# MPPTBatteryCharger.net
KiCad netlist of a schematic drawn in EAGLE
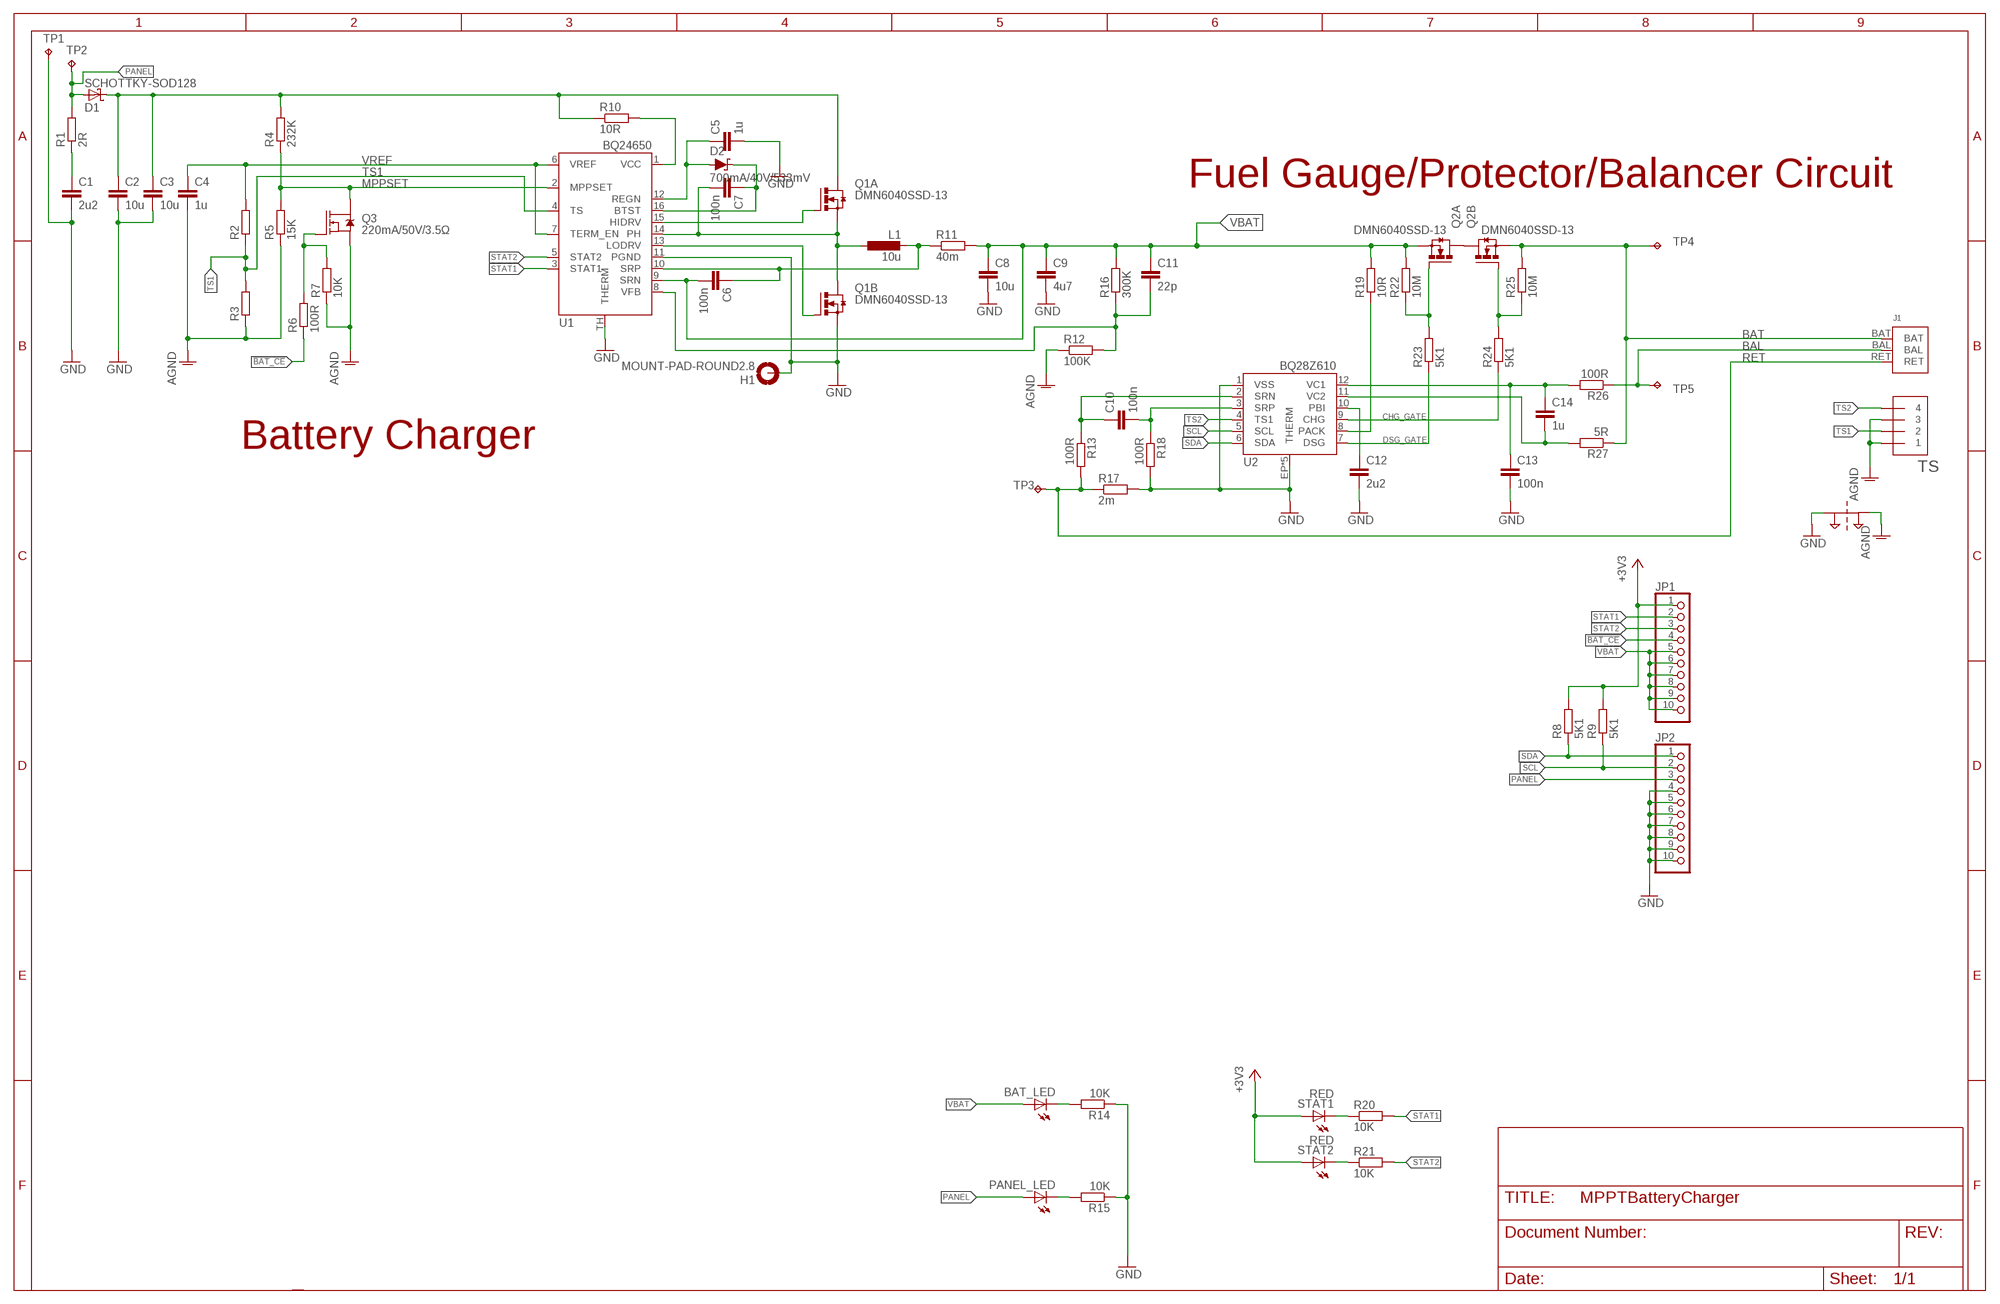
[diagram p0: schematic, sheet 1]

(export (version "E")
  (design (tool "Eeschema 10.0.6"))
  (components
    (comp (ref "BAT_LED")
      (value "LEDCHIP-LED0603")
      (footprint "eagle-import:CHIP-LED0603")
      (libsource (lib "eagle-import") (part "LEDCHIP-LED0603"))
    )
    (comp (ref "C1")
      (value "2u2")
      (footprint "eagle-import:C0603")
      (libsource (lib "eagle-import") (part "C-EUC0603"))
    )
    (comp (ref "C2")
      (value "10u")
      (footprint "eagle-import:C1210")
      (libsource (lib "eagle-import") (part "C-EUC1210"))
    )
    (comp (ref "C3")
      (value "10u")
      (footprint "eagle-import:C1210")
      (libsource (lib "eagle-import") (part "C-EUC1210"))
    )
    (comp (ref "C4")
      (value "1u")
      (footprint "eagle-import:C0603")
      (libsource (lib "eagle-import") (part "C-EUC0603"))
    )
    (comp (ref "C5")
      (value "1u")
      (footprint "eagle-import:C0603")
      (libsource (lib "eagle-import") (part "C-EUC0603"))
    )
    (comp (ref "C6")
      (value "100n")
      (footprint "eagle-import:C0603")
      (libsource (lib "eagle-import") (part "C-EUC0603"))
    )
    (comp (ref "C7")
      (value "100n")
      (footprint "eagle-import:C0603")
      (libsource (lib "eagle-import") (part "C-EUC0603"))
    )
    (comp (ref "C8")
      (value "10u")
      (footprint "eagle-import:C1210")
      (libsource (lib "eagle-import") (part "C-EUC1210"))
    )
    (comp (ref "C9")
      (value "4u7")
      (footprint "eagle-import:C1210")
      (libsource (lib "eagle-import") (part "C-EUC1210"))
    )
    (comp (ref "C10")
      (value "100n")
      (footprint "eagle-import:C0603")
      (libsource (lib "eagle-import") (part "C-EUC0603"))
    )
    (comp (ref "C11")
      (value "22p")
      (footprint "eagle-import:C0603")
      (libsource (lib "eagle-import") (part "C-EUC0603"))
    )
    (comp (ref "C12")
      (value "2u2")
      (footprint "eagle-import:C0603")
      (libsource (lib "eagle-import") (part "C-EUC0603"))
    )
    (comp (ref "C13")
      (value "100n")
      (footprint "eagle-import:C0603")
      (libsource (lib "eagle-import") (part "C-EUC0603"))
    )
    (comp (ref "C14")
      (value "1u")
      (footprint "eagle-import:C0603")
      (libsource (lib "eagle-import") (part "C-EUC0603"))
    )
    (comp (ref "D1")
      (value "SCHOTTKY-SOD128")
      (footprint "eagle-import:SOD-128")
      (libsource (lib "eagle-import") (part "SCHOTTKY-SOD128"))
    )
    (comp (ref "D2")
      (value "700mA/40V/533mV")
      (footprint "eagle-import:SOT23-3")
      (libsource (lib "eagle-import") (part "DIODE-SCHOTTKY-ZLLS500"))
    )
    (comp (ref "H1")
      (value "MOUNT-PAD-ROUND2.8")
      (footprint "eagle-import:2,8-PAD")
      (libsource (lib "eagle-import") (part "MOUNT-PAD-ROUND2.8"))
    )
    (comp (ref "J1")
      (value "2S-BATTERYSMD")
      (footprint "eagle-import:JST-XH3-SMD")
      (libsource (lib "eagle-import") (part "2S-BATTERYSMD"))
    )
    (comp (ref "JP1")
      (value "PINHD-1X10")
      (footprint "eagle-import:1X10")
      (libsource (lib "eagle-import") (part "PINHD-1X10"))
    )
    (comp (ref "JP2")
      (value "PINHD-1X10")
      (footprint "eagle-import:1X10")
      (libsource (lib "eagle-import") (part "PINHD-1X10"))
    )
    (comp (ref "L1")
      (value "10u")
      (footprint "eagle-import:DG6050")
      (libsource (lib "eagle-import") (part "INDUCTOR-DG6050"))
    )
    (comp (ref "PANEL_LED")
      (value "LEDCHIP-LED0603")
      (footprint "eagle-import:CHIP-LED0603")
      (libsource (lib "eagle-import") (part "LEDCHIP-LED0603"))
    )
    (comp (ref "Q1")
      (value "DMN6040SSD-13")
      (footprint "eagle-import:SO-08")
      (libsource (lib "eagle-import") (part "IRF8313P"))
    )
    (comp (ref "Q2")
      (value "DMN6040SSD-13")
      (footprint "eagle-import:SO-08")
      (libsource (lib "eagle-import") (part "IRF8313P"))
    )
    (comp (ref "Q3")
      (value "220mA/50V/3.5Ω")
      (footprint "eagle-import:SOT23-3")
      (libsource (lib "eagle-import") (part "MOSFET-NCH-BSS138"))
    )
    (comp (ref "R1")
      (value "2R")
      (footprint "eagle-import:R0603")
      (libsource (lib "eagle-import") (part "R-EU_R0603"))
    )
    (comp (ref "R2")
      (value "R-EU_R0603")
      (footprint "eagle-import:R0603")
      (libsource (lib "eagle-import") (part "R-EU_R0603"))
    )
    (comp (ref "R3")
      (value "R-EU_R0603")
      (footprint "eagle-import:R0603")
      (libsource (lib "eagle-import") (part "R-EU_R0603"))
    )
    (comp (ref "R4")
      (value "232K")
      (footprint "eagle-import:R0603")
      (libsource (lib "eagle-import") (part "R-EU_R0603"))
    )
    (comp (ref "R5")
      (value "15K")
      (footprint "eagle-import:R0603")
      (libsource (lib "eagle-import") (part "R-EU_R0603"))
    )
    (comp (ref "R6")
      (value "100R")
      (footprint "eagle-import:R0603")
      (libsource (lib "eagle-import") (part "R-EU_R0603"))
    )
    (comp (ref "R7")
      (value "10K")
      (footprint "eagle-import:R0603")
      (libsource (lib "eagle-import") (part "R-EU_R0603"))
    )
    (comp (ref "R8")
      (value "5K1")
      (footprint "eagle-import:R0603")
      (libsource (lib "eagle-import") (part "R-EU_R0603"))
    )
    (comp (ref "R9")
      (value "5K1")
      (footprint "eagle-import:R0603")
      (libsource (lib "eagle-import") (part "R-EU_R0603"))
    )
    (comp (ref "R10")
      (value "10R")
      (footprint "eagle-import:R1206")
      (libsource (lib "eagle-import") (part "R-EU_R1206"))
    )
    (comp (ref "R11")
      (value "40m")
      (footprint "eagle-import:R2512")
      (libsource (lib "eagle-import") (part "R-EU_R2512"))
    )
    (comp (ref "R12")
      (value "100K")
      (footprint "eagle-import:R0603")
      (libsource (lib "eagle-import") (part "R-EU_R0603"))
    )
    (comp (ref "R13")
      (value "100R")
      (footprint "eagle-import:R0603")
      (libsource (lib "eagle-import") (part "R-EU_R0603"))
    )
    (comp (ref "R14")
      (value "10K")
      (footprint "eagle-import:R0603")
      (libsource (lib "eagle-import") (part "R-EU_R0603"))
    )
    (comp (ref "R15")
      (value "10K")
      (footprint "eagle-import:R0603")
      (libsource (lib "eagle-import") (part "R-EU_R0603"))
    )
    (comp (ref "R16")
      (value "300K")
      (footprint "eagle-import:R0603")
      (libsource (lib "eagle-import") (part "R-EU_R0603"))
    )
    (comp (ref "R17")
      (value "2m")
      (footprint "eagle-import:R2512")
      (libsource (lib "eagle-import") (part "R-EU_R2512"))
    )
    (comp (ref "R18")
      (value "100R")
      (footprint "eagle-import:R0603")
      (libsource (lib "eagle-import") (part "R-EU_R0603"))
    )
    (comp (ref "R19")
      (value "10R")
      (footprint "eagle-import:R0603")
      (libsource (lib "eagle-import") (part "R-EU_R0603"))
    )
    (comp (ref "R20")
      (value "10K")
      (footprint "eagle-import:R0603")
      (libsource (lib "eagle-import") (part "R-EU_R0603"))
    )
    (comp (ref "R21")
      (value "10K")
      (footprint "eagle-import:R0603")
      (libsource (lib "eagle-import") (part "R-EU_R0603"))
    )
    (comp (ref "R22")
      (value "10M")
      (footprint "eagle-import:R0603")
      (libsource (lib "eagle-import") (part "R-EU_R0603"))
    )
    (comp (ref "R23")
      (value "5K1")
      (footprint "eagle-import:R0603")
      (libsource (lib "eagle-import") (part "R-EU_R0603"))
    )
    (comp (ref "R24")
      (value "5K1")
      (footprint "eagle-import:R0603")
      (libsource (lib "eagle-import") (part "R-EU_R0603"))
    )
    (comp (ref "R25")
      (value "10M")
      (footprint "eagle-import:R0603")
      (libsource (lib "eagle-import") (part "R-EU_R0603"))
    )
    (comp (ref "R26")
      (value "100R")
      (footprint "eagle-import:R0603")
      (libsource (lib "eagle-import") (part "R-EU_R0603"))
    )
    (comp (ref "R27")
      (value "5R")
      (footprint "eagle-import:R0603")
      (libsource (lib "eagle-import") (part "R-EU_R0603"))
    )
    (comp (ref "STAT1")
      (value "RED")
      (footprint "eagle-import:CHIP-LED0603")
      (libsource (lib "eagle-import") (part "LEDCHIP-LED0603"))
    )
    (comp (ref "STAT2")
      (value "RED")
      (footprint "eagle-import:CHIP-LED0603")
      (libsource (lib "eagle-import") (part "LEDCHIP-LED0603"))
    )
    (comp (ref "SUPPLY1")
      (value "2PT_GND_TIE")
      (footprint "eagle-import:2PT_GND_TIE")
      (libsource (lib "eagle-import") (part "2PT_GND_TIE"))
    )
    (comp (ref "TP1")
      (value "TPPAD1-13Y")
      (footprint "eagle-import:P1-13Y")
      (libsource (lib "eagle-import") (part "TPPAD1-13Y"))
    )
    (comp (ref "TP2")
      (value "TPPAD1-13Y")
      (footprint "eagle-import:P1-13Y")
      (libsource (lib "eagle-import") (part "TPPAD1-13Y"))
    )
    (comp (ref "TP3")
      (value "TPPAD1-13Y")
      (footprint "eagle-import:P1-13Y")
      (libsource (lib "eagle-import") (part "TPPAD1-13Y"))
    )
    (comp (ref "TP4")
      (value "TPPAD1-13Y")
      (footprint "eagle-import:P1-13Y")
      (libsource (lib "eagle-import") (part "TPPAD1-13Y"))
    )
    (comp (ref "TP5")
      (value "TPPAD1-13Y")
      (footprint "eagle-import:P1-13Y")
      (libsource (lib "eagle-import") (part "TPPAD1-13Y"))
    )
    (comp (ref "TS")
      (value "STRAWSON_EAGLE_LIB_JST_SH_4")
      (footprint "eagle-import:STRAWSON_EAGLE_LIB_JST_SH_4_SMD")
      (libsource (lib "eagle-import") (part "STRAWSON_EAGLE_LIB_JST_SH_4"))
    )
    (comp (ref "U1")
      (value "BQ24650")
      (footprint "eagle-import:QFN16")
      (libsource (lib "eagle-import") (part "BQ24650"))
    )
    (comp (ref "U2")
      (value "BQ28Z610")
      (footprint "eagle-import:PDSO-N12")
      (libsource (lib "eagle-import") (part "BQ28Z610"))
    )
  )
  (nets
    (net (code "1") (name "+3V3") (class "Default")
      (node (ref "JP1") (pin "1") (pinfunction "1_1") (pintype "passive"))
      (node (ref "R8") (pin "2") (pinfunction "2_2") (pintype "passive"))
      (node (ref "R9") (pin "2") (pinfunction "2_2") (pintype "passive"))
      (node (ref "STAT1") (pin "A") (pinfunction "A_A") (pintype "passive"))
      (node (ref "STAT2") (pin "A") (pinfunction "A_A") (pintype "passive"))
    )
    (net (code "2") (name "/BAL") (class "Default")
      (node (ref "J1") (pin "BAL") (pinfunction "BAL_BAL") (pintype "bidirectional"))
      (node (ref "R26") (pin "1") (pinfunction "1_1") (pintype "passive"))
      (node (ref "TP5") (pin "TP") (pinfunction "TP_TP") (pintype "input"))
    )
    (net (code "3") (name "/BAT") (class "Default")
      (node (ref "J1") (pin "BAT") (pinfunction "BAT_BAT") (pintype "bidirectional"))
      (node (ref "Q2") (pin "1") (pinfunction "S_1") (pintype "passive"))
      (node (ref "R25") (pin "2") (pinfunction "2_2") (pintype "passive"))
      (node (ref "R27") (pin "1") (pinfunction "1_1") (pintype "passive"))
      (node (ref "TP4") (pin "TP") (pinfunction "TP_TP") (pintype "input"))
    )
    (net (code "4") (name "/CHG_GATE") (class "Default")
      (node (ref "R24") (pin "1") (pinfunction "1_1") (pintype "passive"))
      (node (ref "U2") (pin "9") (pinfunction "CHG_9") (pintype "bidirectional"))
    )
    (net (code "5") (name "/DSG_GATE") (class "Default")
      (node (ref "R23") (pin "1") (pinfunction "1_1") (pintype "passive"))
      (node (ref "U2") (pin "7") (pinfunction "DSG_7") (pintype "bidirectional"))
    )
    (net (code "6") (name "/MPPSET") (class "Default")
      (node (ref "Q3") (pin "3") (pinfunction "D_3") (pintype "bidirectional"))
      (node (ref "R4") (pin "1") (pinfunction "1_1") (pintype "passive"))
      (node (ref "R5") (pin "2") (pinfunction "2_2") (pintype "passive"))
      (node (ref "U1") (pin "2") (pinfunction "MPPSET_2") (pintype "bidirectional"))
    )
    (net (code "7") (name "/RET") (class "Default")
      (node (ref "J1") (pin "RET") (pinfunction "RET_RET") (pintype "bidirectional"))
      (node (ref "R13") (pin "2") (pinfunction "2_2") (pintype "passive"))
      (node (ref "R17") (pin "1") (pinfunction "1_1") (pintype "passive"))
      (node (ref "TP3") (pin "TP") (pinfunction "TP_TP") (pintype "input"))
    )
    (net (code "8") (name "/VREF") (class "Default")
      (node (ref "C4") (pin "1") (pinfunction "1_1") (pintype "passive"))
      (node (ref "R2") (pin "2") (pinfunction "2_2") (pintype "passive"))
      (node (ref "U1") (pin "6") (pinfunction "VREF_6") (pintype "bidirectional"))
      (node (ref "U1") (pin "7") (pinfunction "TERM_EN_7") (pintype "bidirectional"))
    )
    (net (code "9") (name "/~{BAT_CE}") (class "Default")
      (node (ref "JP1") (pin "4") (pinfunction "4_4") (pintype "passive"))
      (node (ref "R6") (pin "1") (pinfunction "1_1") (pintype "passive"))
    )
    (net (code "10") (name "AGND") (class "Default")
      (node (ref "C4") (pin "2") (pinfunction "2_2") (pintype "passive"))
      (node (ref "Q3") (pin "2") (pinfunction "S_2") (pintype "bidirectional"))
      (node (ref "R12") (pin "1") (pinfunction "1_1") (pintype "passive"))
      (node (ref "R3") (pin "1") (pinfunction "1_1") (pintype "passive"))
      (node (ref "R5") (pin "1") (pinfunction "1_1") (pintype "passive"))
      (node (ref "R7") (pin "1") (pinfunction "1_1") (pintype "passive"))
      (node (ref "SUPPLY1") (pin "P$2") (pinfunction "P$2_P$2") (pintype "bidirectional"))
      (node (ref "TS") (pin "1") (pinfunction "1_1") (pintype "bidirectional"))
      (node (ref "TS") (pin "3") (pinfunction "3_3") (pintype "bidirectional"))
    )
    (net (code "11") (name "GND") (class "Default")
      (node (ref "C1") (pin "2") (pinfunction "2_2") (pintype "passive"))
      (node (ref "C12") (pin "2") (pinfunction "2_2") (pintype "passive"))
      (node (ref "C13") (pin "2") (pinfunction "2_2") (pintype "passive"))
      (node (ref "C2") (pin "2") (pinfunction "2_2") (pintype "passive"))
      (node (ref "C3") (pin "2") (pinfunction "2_2") (pintype "passive"))
      (node (ref "C5") (pin "2") (pinfunction "2_2") (pintype "passive"))
      (node (ref "C8") (pin "2") (pinfunction "2_2") (pintype "passive"))
      (node (ref "C9") (pin "2") (pinfunction "2_2") (pintype "passive"))
      (node (ref "H1") (pin "B2,8") (pinfunction "MOUNT_B2,8") (pintype "passive"))
      (node (ref "JP2") (pin "10") (pinfunction "10_10") (pintype "passive"))
      (node (ref "JP2") (pin "4") (pinfunction "4_4") (pintype "passive"))
      (node (ref "JP2") (pin "5") (pinfunction "5_5") (pintype "passive"))
      (node (ref "JP2") (pin "6") (pinfunction "6_6") (pintype "passive"))
      (node (ref "JP2") (pin "7") (pinfunction "7_7") (pintype "passive"))
      (node (ref "JP2") (pin "8") (pinfunction "8_8") (pintype "passive"))
      (node (ref "JP2") (pin "9") (pinfunction "9_9") (pintype "passive"))
      (node (ref "Q1") (pin "1") (pinfunction "S_1") (pintype "passive"))
      (node (ref "R14") (pin "1") (pinfunction "1_1") (pintype "passive"))
      (node (ref "R15") (pin "1") (pinfunction "1_1") (pintype "passive"))
      (node (ref "R17") (pin "2") (pinfunction "2_2") (pintype "passive"))
      (node (ref "R18") (pin "2") (pinfunction "2_2") (pintype "passive"))
      (node (ref "SUPPLY1") (pin "P$1") (pinfunction "P$1_P$1") (pintype "bidirectional"))
      (node (ref "TP1") (pin "TP") (pinfunction "TP_TP") (pintype "input"))
      (node (ref "U1") (pin "11") (pinfunction "PGND_11") (pintype "bidirectional"))
      (node (ref "U1") (pin "TH") (pinfunction "THERM_TH") (pintype "bidirectional"))
      (node (ref "U2") (pin "1") (pinfunction "VSS_1") (pintype "bidirectional"))
      (node (ref "U2") (pin "EP") (pinfunction "THERM_EP") (pintype "bidirectional"))
      (node (ref "U2") (pin "EP1") (pinfunction "THERM_EP1") (pintype "bidirectional"))
      (node (ref "U2") (pin "EP2") (pinfunction "THERM_EP2") (pintype "bidirectional"))
      (node (ref "U2") (pin "EP3") (pinfunction "THERM_EP3") (pintype "bidirectional"))
      (node (ref "U2") (pin "EP4") (pinfunction "THERM_EP4") (pintype "bidirectional"))
    )
    (net (code "12") (name "Net-(BAT_LED-PadC)") (class "Default")
      (node (ref "BAT_LED") (pin "C") (pinfunction "C_C") (pintype "passive"))
      (node (ref "R14") (pin "2") (pinfunction "2_2") (pintype "passive"))
    )
    (net (code "13") (name "Net-(C1-Pad1)") (class "Default")
      (node (ref "C1") (pin "1") (pinfunction "1_1") (pintype "passive"))
      (node (ref "R1") (pin "1") (pinfunction "1_1") (pintype "passive"))
    )
    (net (code "14") (name "Net-(C2-Pad1)") (class "Default")
      (node (ref "C2") (pin "1") (pinfunction "1_1") (pintype "passive"))
      (node (ref "C3") (pin "1") (pinfunction "1_1") (pintype "passive"))
      (node (ref "D1") (pin "C") (pinfunction "C_C") (pintype "passive"))
      (node (ref "Q1") (pin "5") (pinfunction "D_5") (pintype "passive"))
      (node (ref "Q1") (pin "6") (pinfunction "D_6") (pintype "passive"))
      (node (ref "R10") (pin "1") (pinfunction "1_1") (pintype "passive"))
      (node (ref "R4") (pin "2") (pinfunction "2_2") (pintype "passive"))
    )
    (net (code "15") (name "Net-(D2-A)") (class "Default")
      (node (ref "C5") (pin "1") (pinfunction "1_1") (pintype "passive"))
      (node (ref "D2") (pin "1") (pinfunction "A_1") (pintype "passive"))
      (node (ref "U1") (pin "12") (pinfunction "REGN_12") (pintype "bidirectional"))
    )
    (net (code "16") (name "Net-(D2-C)") (class "Default")
      (node (ref "C7") (pin "1") (pinfunction "1_1") (pintype "passive"))
      (node (ref "D2") (pin "3") (pinfunction "C_3") (pintype "passive"))
      (node (ref "U1") (pin "16") (pinfunction "BTST_16") (pintype "bidirectional"))
    )
    (net (code "17") (name "Net-(PANEL_LED-PadC)") (class "Default")
      (node (ref "PANEL_LED") (pin "C") (pinfunction "C_C") (pintype "passive"))
      (node (ref "R15") (pin "2") (pinfunction "2_2") (pintype "passive"))
    )
    (net (code "18") (name "Net-(Q1A-G)") (class "Default")
      (node (ref "Q1") (pin "4") (pinfunction "G_4") (pintype "passive"))
      (node (ref "U1") (pin "15") (pinfunction "HIDRV_15") (pintype "bidirectional"))
    )
    (net (code "19") (name "Net-(Q1A-S)") (class "Default")
      (node (ref "C7") (pin "2") (pinfunction "2_2") (pintype "passive"))
      (node (ref "L1") (pin "1") (pinfunction "1_1") (pintype "passive"))
      (node (ref "Q1") (pin "3") (pinfunction "S_3") (pintype "passive"))
      (node (ref "Q1") (pin "7") (pinfunction "D_7") (pintype "passive"))
      (node (ref "Q1") (pin "8") (pinfunction "D_8") (pintype "passive"))
      (node (ref "U1") (pin "14") (pinfunction "PH_14") (pintype "bidirectional"))
    )
    (net (code "20") (name "Net-(Q1B-G)") (class "Default")
      (node (ref "Q1") (pin "2") (pinfunction "G_2") (pintype "passive"))
      (node (ref "U1") (pin "13") (pinfunction "LODRV_13") (pintype "bidirectional"))
    )
    (net (code "21") (name "Net-(Q2A-D-Pad5)") (class "Default")
      (node (ref "Q2") (pin "5") (pinfunction "D_5") (pintype "passive"))
      (node (ref "Q2") (pin "6") (pinfunction "D_6") (pintype "passive"))
      (node (ref "Q2") (pin "7") (pinfunction "D_7") (pintype "passive"))
      (node (ref "Q2") (pin "8") (pinfunction "D_8") (pintype "passive"))
    )
    (net (code "22") (name "Net-(Q2A-G)") (class "Default")
      (node (ref "Q2") (pin "4") (pinfunction "G_4") (pintype "passive"))
      (node (ref "R22") (pin "1") (pinfunction "1_1") (pintype "passive"))
      (node (ref "R23") (pin "2") (pinfunction "2_2") (pintype "passive"))
    )
    (net (code "23") (name "Net-(Q2B-G)") (class "Default")
      (node (ref "Q2") (pin "2") (pinfunction "G_2") (pintype "passive"))
      (node (ref "R24") (pin "2") (pinfunction "2_2") (pintype "passive"))
      (node (ref "R25") (pin "1") (pinfunction "1_1") (pintype "passive"))
    )
    (net (code "24") (name "Net-(Q3-G)") (class "Default")
      (node (ref "Q3") (pin "1") (pinfunction "G_1") (pintype "bidirectional"))
      (node (ref "R6") (pin "2") (pinfunction "2_2") (pintype "passive"))
      (node (ref "R7") (pin "2") (pinfunction "2_2") (pintype "passive"))
    )
    (net (code "25") (name "Net-(R20-Pad1)") (class "Default")
      (node (ref "R20") (pin "1") (pinfunction "1_1") (pintype "passive"))
      (node (ref "STAT1") (pin "C") (pinfunction "C_C") (pintype "passive"))
    )
    (net (code "26") (name "Net-(R21-Pad1)") (class "Default")
      (node (ref "R21") (pin "1") (pinfunction "1_1") (pintype "passive"))
      (node (ref "STAT2") (pin "C") (pinfunction "C_C") (pintype "passive"))
    )
    (net (code "27") (name "Net-(U1-SRP)") (class "Default")
      (node (ref "C6") (pin "1") (pinfunction "1_1") (pintype "passive"))
      (node (ref "L1") (pin "2") (pinfunction "2_2") (pintype "passive"))
      (node (ref "R11") (pin "1") (pinfunction "1_1") (pintype "passive"))
      (node (ref "U1") (pin "10") (pinfunction "SRP_10") (pintype "bidirectional"))
    )
    (net (code "28") (name "Net-(U1-VCC)") (class "Default")
      (node (ref "R10") (pin "2") (pinfunction "2_2") (pintype "passive"))
      (node (ref "U1") (pin "1") (pinfunction "VCC_1") (pintype "bidirectional"))
    )
    (net (code "29") (name "Net-(U1-VFB)") (class "Default")
      (node (ref "C11") (pin "2") (pinfunction "2_2") (pintype "passive"))
      (node (ref "R12") (pin "2") (pinfunction "2_2") (pintype "passive"))
      (node (ref "R16") (pin "1") (pinfunction "1_1") (pintype "passive"))
      (node (ref "U1") (pin "8") (pinfunction "VFB_8") (pintype "bidirectional"))
    )
    (net (code "30") (name "Net-(U2-PACK)") (class "Default")
      (node (ref "R19") (pin "1") (pinfunction "1_1") (pintype "passive"))
      (node (ref "U2") (pin "8") (pinfunction "PACK_8") (pintype "bidirectional"))
    )
    (net (code "31") (name "Net-(U2-PBI)") (class "Default")
      (node (ref "C12") (pin "1") (pinfunction "1_1") (pintype "passive"))
      (node (ref "U2") (pin "10") (pinfunction "PBI_10") (pintype "bidirectional"))
    )
    (net (code "32") (name "Net-(U2-SRN)") (class "Default")
      (node (ref "C10") (pin "1") (pinfunction "1_1") (pintype "passive"))
      (node (ref "R13") (pin "1") (pinfunction "1_1") (pintype "passive"))
      (node (ref "U2") (pin "2") (pinfunction "SRN_2") (pintype "bidirectional"))
    )
    (net (code "33") (name "Net-(U2-SRP)") (class "Default")
      (node (ref "C10") (pin "2") (pinfunction "2_2") (pintype "passive"))
      (node (ref "R18") (pin "1") (pinfunction "1_1") (pintype "passive"))
      (node (ref "U2") (pin "3") (pinfunction "SRP_3") (pintype "bidirectional"))
    )
    (net (code "34") (name "Net-(U2-VC1)") (class "Default")
      (node (ref "C13") (pin "1") (pinfunction "1_1") (pintype "passive"))
      (node (ref "C14") (pin "1") (pinfunction "1_1") (pintype "passive"))
      (node (ref "R26") (pin "2") (pinfunction "2_2") (pintype "passive"))
      (node (ref "U2") (pin "12") (pinfunction "VC1_12") (pintype "bidirectional"))
    )
    (net (code "35") (name "Net-(U2-VC2)") (class "Default")
      (node (ref "C14") (pin "2") (pinfunction "2_2") (pintype "passive"))
      (node (ref "R27") (pin "2") (pinfunction "2_2") (pintype "passive"))
      (node (ref "U2") (pin "11") (pinfunction "VC2_11") (pintype "bidirectional"))
    )
    (net (code "36") (name "PANEL") (class "Default")
      (node (ref "D1") (pin "A") (pinfunction "A_A") (pintype "passive"))
      (node (ref "JP2") (pin "3") (pinfunction "3_3") (pintype "passive"))
      (node (ref "PANEL_LED") (pin "A") (pinfunction "A_A") (pintype "passive"))
      (node (ref "R1") (pin "2") (pinfunction "2_2") (pintype "passive"))
      (node (ref "TP2") (pin "TP") (pinfunction "TP_TP") (pintype "input"))
    )
    (net (code "37") (name "SCL") (class "Default")
      (node (ref "JP2") (pin "2") (pinfunction "2_2") (pintype "passive"))
      (node (ref "R9") (pin "1") (pinfunction "1_1") (pintype "passive"))
      (node (ref "U2") (pin "5") (pinfunction "SCL_5") (pintype "bidirectional"))
    )
    (net (code "38") (name "SDA") (class "Default")
      (node (ref "JP2") (pin "1") (pinfunction "1_1") (pintype "passive"))
      (node (ref "R8") (pin "1") (pinfunction "1_1") (pintype "passive"))
      (node (ref "U2") (pin "6") (pinfunction "SDA_6") (pintype "bidirectional"))
    )
    (net (code "39") (name "STAT1") (class "Default")
      (node (ref "JP1") (pin "2") (pinfunction "2_2") (pintype "passive"))
      (node (ref "R20") (pin "2") (pinfunction "2_2") (pintype "passive"))
      (node (ref "U1") (pin "3") (pinfunction "STAT1_3") (pintype "bidirectional"))
    )
    (net (code "40") (name "STAT2") (class "Default")
      (node (ref "JP1") (pin "3") (pinfunction "3_3") (pintype "passive"))
      (node (ref "R21") (pin "2") (pinfunction "2_2") (pintype "passive"))
      (node (ref "U1") (pin "5") (pinfunction "STAT2_5") (pintype "bidirectional"))
    )
    (net (code "41") (name "TS1") (class "Default")
      (node (ref "R2") (pin "1") (pinfunction "1_1") (pintype "passive"))
      (node (ref "R3") (pin "2") (pinfunction "2_2") (pintype "passive"))
      (node (ref "TS") (pin "2") (pinfunction "2_2") (pintype "bidirectional"))
      (node (ref "U1") (pin "4") (pinfunction "TS_4") (pintype "bidirectional"))
    )
    (net (code "42") (name "TS2") (class "Default")
      (node (ref "TS") (pin "4") (pinfunction "4_4") (pintype "bidirectional"))
      (node (ref "U2") (pin "4") (pinfunction "TS1_4") (pintype "bidirectional"))
    )
    (net (code "43") (name "VBAT") (class "Default")
      (node (ref "BAT_LED") (pin "A") (pinfunction "A_A") (pintype "passive"))
      (node (ref "C11") (pin "1") (pinfunction "1_1") (pintype "passive"))
      (node (ref "C6") (pin "2") (pinfunction "2_2") (pintype "passive"))
      (node (ref "C8") (pin "1") (pinfunction "1_1") (pintype "passive"))
      (node (ref "C9") (pin "1") (pinfunction "1_1") (pintype "passive"))
      (node (ref "JP1") (pin "10") (pinfunction "10_10") (pintype "passive"))
      (node (ref "JP1") (pin "5") (pinfunction "5_5") (pintype "passive"))
      (node (ref "JP1") (pin "6") (pinfunction "6_6") (pintype "passive"))
      (node (ref "JP1") (pin "7") (pinfunction "7_7") (pintype "passive"))
      (node (ref "JP1") (pin "8") (pinfunction "8_8") (pintype "passive"))
      (node (ref "JP1") (pin "9") (pinfunction "9_9") (pintype "passive"))
      (node (ref "Q2") (pin "3") (pinfunction "S_3") (pintype "passive"))
      (node (ref "R11") (pin "2") (pinfunction "2_2") (pintype "passive"))
      (node (ref "R16") (pin "2") (pinfunction "2_2") (pintype "passive"))
      (node (ref "R19") (pin "2") (pinfunction "2_2") (pintype "passive"))
      (node (ref "R22") (pin "2") (pinfunction "2_2") (pintype "passive"))
      (node (ref "U1") (pin "9") (pinfunction "SRN_9") (pintype "bidirectional"))
    )
  )
)
